# iDProxRev2.net
KiCad netlist of a schematic drawn in Altium Designer
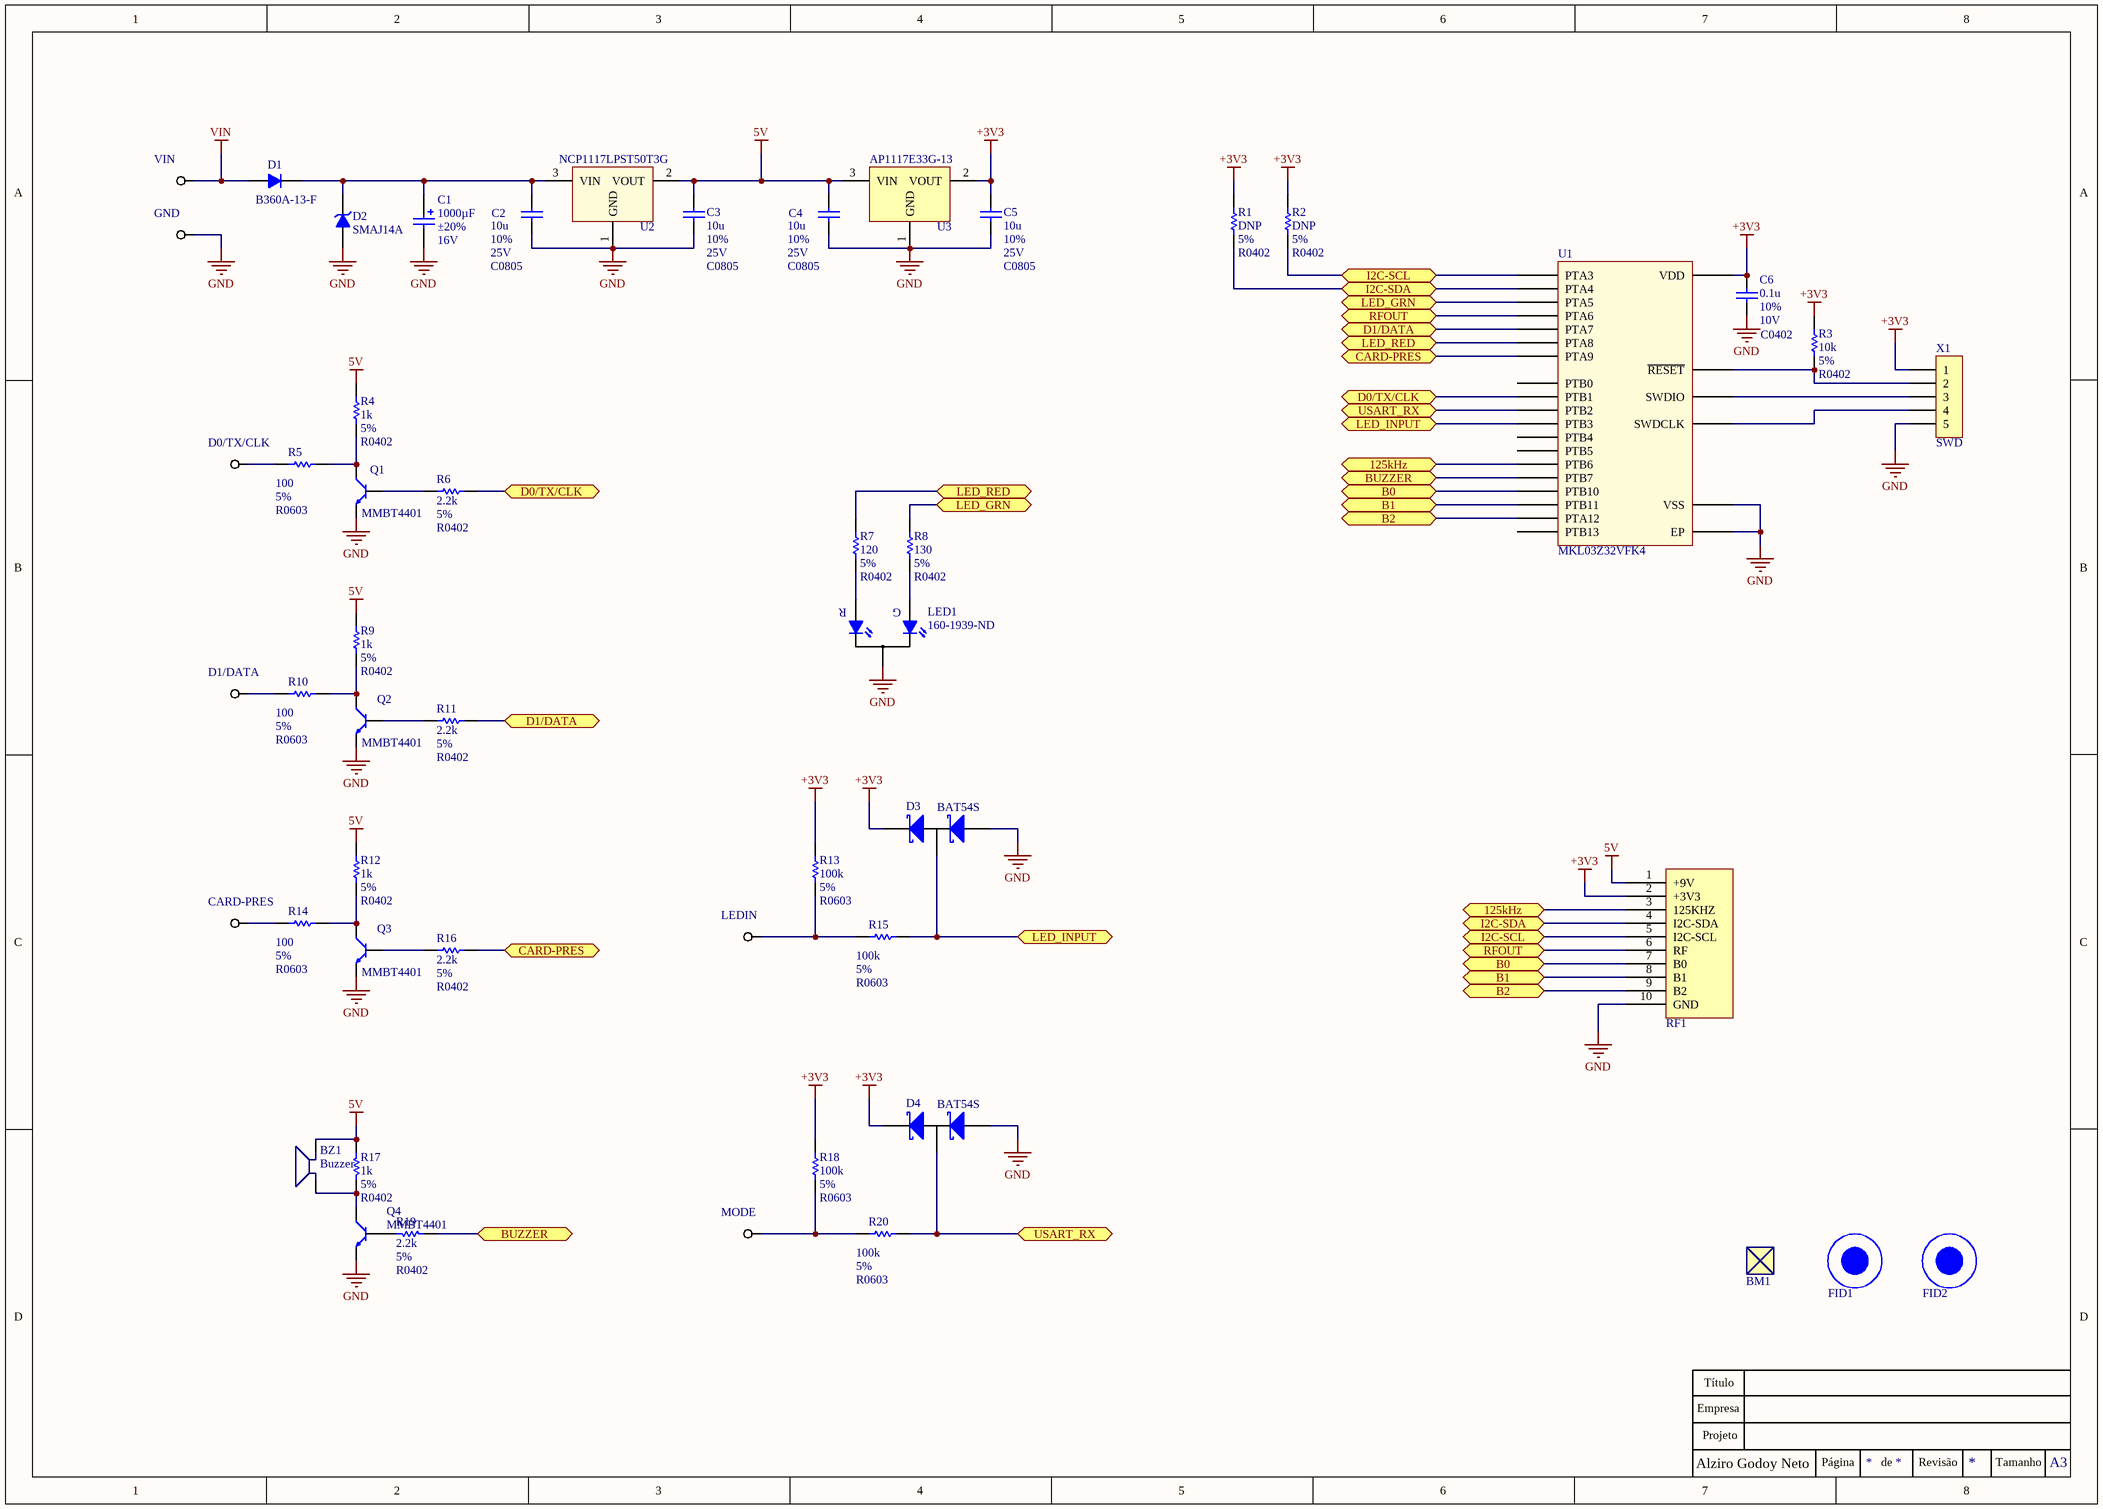
[diagram p0: iDProxRev2.SchDoc]

(export (version "E")
  (design (tool "Eeschema 10.0.6"))
  (components
    (comp (ref "BM1")
      (value "BADMARK")
      (footprint "BADMARK")
      (description "Bad Mark Indicator")
      (libsource (lib "CiDLib") (part "BADMARK"))
    )
    (comp (ref "BZ1")
      (value "Buzzer")
      (footprint "Buzzer")
      (description "Standard PTH Buzzer")
      (libsource (lib "CiDLib") (part "Buzzer"))
    )
    (comp (ref "C1")
      (value "ESK108M016AH2AA")
      (footprint "ESK108M016AH2AA")
      (description "CAP ALUM 1000UF 20% 16V RADIAL")
      (fields
        (field (name "MANUFACTURER") "Kemet")
        (field (name "CAPACITANCE") "1000µF")
        (field (name "TOLERANCE") "±20%")
        (field (name "VOLTAGE RATING") "16V")
      )
      (libsource (lib "CiDLib") (part "ESK108M016AH2AA"))
    )
    (comp (ref "C2")
      (value "10u")
      (footprint "C0805")
      (description "Capacitor")
      (fields
        (field (name "TOLERANCE") "10%")
        (field (name "MAX VDC") "25V")
        (field (name "Comment") "Cap0805")
      )
      (libsource (lib "CiDLib") (part "Cap0805"))
    )
    (comp (ref "C3")
      (value "10u")
      (footprint "C0805")
      (description "Capacitor")
      (fields
        (field (name "TOLERANCE") "10%")
        (field (name "MAX VDC") "25V")
        (field (name "Comment") "Cap0805")
      )
      (libsource (lib "CiDLib") (part "Cap0805"))
    )
    (comp (ref "C4")
      (value "10u")
      (footprint "C0805")
      (description "Capacitor")
      (fields
        (field (name "TOLERANCE") "10%")
        (field (name "MAX VDC") "25V")
        (field (name "Comment") "Cap0805")
      )
      (libsource (lib "CiDLib") (part "Cap0805"))
    )
    (comp (ref "C5")
      (value "10u")
      (footprint "C0805")
      (description "Capacitor")
      (fields
        (field (name "TOLERANCE") "10%")
        (field (name "MAX VDC") "25V")
        (field (name "Comment") "Cap0805")
      )
      (libsource (lib "CiDLib") (part "Cap0805"))
    )
    (comp (ref "C6")
      (value "0.1u")
      (footprint "C0402")
      (description "Capacitor")
      (fields
        (field (name "TOLERANCE") "10%")
        (field (name "MAX VDC") "10V")
        (field (name "Comment") "Cap0402")
      )
      (libsource (lib "CiDLib") (part "Cap0402"))
    )
    (comp (ref "CARD-PRES") (value "Hole") (footprint "Hole") (libsource (lib "CiDLib") (part "Hole")))
    (comp (ref "D0/TX/CLK") (value "Hole") (footprint "Hole") (libsource (lib "CiDLib") (part "Hole")))
    (comp (ref "D1")
      (value "B360A-13-F")
      (footprint "SMA")
      (description "B360A Diode")
      (fields (field (name "MANUFACTURER") "Diodes Incorporated"))
      (libsource (lib "CiDLib") (part "B360A"))
    )
    (comp (ref "D1/DATA") (value "Hole") (footprint "Hole") (libsource (lib "CiDLib") (part "Hole")))
    (comp (ref "D2")
      (value "SMAJ14A")
      (footprint "SMA")
      (description "TVS DIODE 14VWM 23.2VC SMA")
      (fields (field (name "MANUFACTURER") "Littelfuse Inc."))
      (libsource (lib "CiDLib") (part "SMAJ14A"))
    )
    (comp (ref "D3")
      (value "BAT54S")
      (footprint "SOT23-3")
      (description "DIODE ARRAY SCHOTTKY 30V SOT23")
      (libsource (lib "CiDLib") (part "BAT54S"))
    )
    (comp (ref "D4")
      (value "BAT54S")
      (footprint "SOT23-3")
      (description "DIODE ARRAY SCHOTTKY 30V SOT23")
      (libsource (lib "CiDLib") (part "BAT54S"))
    )
    (comp (ref "FID1")
      (value "FIDUCIAL")
      (footprint "FIDUCIAL-1.5X3")
      (description "Standard fiducial for Control iD boards")
      (libsource (lib "CiDLib") (part "FIDUCIAL"))
    )
    (comp (ref "FID2")
      (value "FIDUCIAL")
      (footprint "FIDUCIAL-1.5X3")
      (description "Standard fiducial for Control iD boards")
      (libsource (lib "CiDLib") (part "FIDUCIAL"))
    )
    (comp (ref "GND") (value "Hole") (footprint "Hole") (libsource (lib "CiDLib") (part "Hole")))
    (comp (ref "LED1")
      (value "LTL1BEKVJNN")
      (footprint "LTL1BEKVJNN")
      (description "LED GRN/RED DIFF 3MM ROUND T/H")
      (fields
        (field (name "MANUFACTURER") "Lite-On Inc.")
        (field (name "SUPPLIER PART NUMBER 1") "160-1939-ND")
      )
      (libsource (lib "CiDLib") (part "LTL1BEKVJNN"))
    )
    (comp (ref "LEDIN") (value "Hole") (footprint "Hole") (libsource (lib "CiDLib") (part "Hole")))
    (comp (ref "MODE") (value "Hole") (footprint "Hole") (libsource (lib "CiDLib") (part "Hole")))
    (comp (ref "Q1")
      (value "MMBT4401")
      (footprint "SOT23-3")
      (description "TRANS NPN 40V 0.6A SOT-23")
      (fields
        (field (name "MANUFACTURER") "ON Semiconductor")
        (field (name "MANUFACTURER PART NUMBER") "MMBT4401LT3G")
      )
      (libsource (lib "CiDLib") (part "MMBT4401LT3G"))
    )
    (comp (ref "Q2")
      (value "MMBT4401")
      (footprint "SOT23-3")
      (description "TRANS NPN 40V 0.6A SOT-23")
      (fields
        (field (name "MANUFACTURER") "ON Semiconductor")
        (field (name "MANUFACTURER PART NUMBER") "MMBT4401LT3G")
      )
      (libsource (lib "CiDLib") (part "MMBT4401LT3G"))
    )
    (comp (ref "Q3")
      (value "MMBT4401")
      (footprint "SOT23-3")
      (description "TRANS NPN 40V 0.6A SOT-23")
      (fields
        (field (name "MANUFACTURER") "ON Semiconductor")
        (field (name "MANUFACTURER PART NUMBER") "MMBT4401LT3G")
      )
      (libsource (lib "CiDLib") (part "MMBT4401LT3G"))
    )
    (comp (ref "Q4")
      (value "MMBT4401")
      (footprint "SOT23-3")
      (description "TRANS NPN 40V 0.6A SOT-23")
      (fields
        (field (name "MANUFACTURER") "ON Semiconductor")
        (field (name "MANUFACTURER PART NUMBER") "MMBT4401LT3G")
      )
      (libsource (lib "CiDLib") (part "MMBT4401LT3G"))
    )
    (comp (ref "R1")
      (value "DNP")
      (footprint "R0402")
      (description "Resistor")
      (fields (field (name "TOLERANCE") "5%") (field (name "Comment") "Res0402"))
      (libsource (lib "CiDLib") (part "Res0402"))
    )
    (comp (ref "R2")
      (value "DNP")
      (footprint "R0402")
      (description "Resistor")
      (fields (field (name "TOLERANCE") "5%") (field (name "Comment") "Res0402"))
      (libsource (lib "CiDLib") (part "Res0402"))
    )
    (comp (ref "R3")
      (value "10k")
      (footprint "R0402")
      (description "Resistor")
      (fields (field (name "TOLERANCE") "5%") (field (name "Comment") "Res0402"))
      (libsource (lib "CiDLib") (part "Res0402"))
    )
    (comp (ref "R4")
      (value "1k")
      (footprint "R0402")
      (description "Resistor")
      (fields (field (name "TOLERANCE") "5%") (field (name "Comment") "Res0402"))
      (libsource (lib "CiDLib") (part "Res0402"))
    )
    (comp (ref "R5")
      (value "100")
      (footprint "R0603")
      (description "Resistor")
      (fields (field (name "TOLERANCE") "5%") (field (name "Comment") "Res0603"))
      (libsource (lib "CiDLib") (part "Res0603"))
    )
    (comp (ref "R6")
      (value "2.2k")
      (footprint "R0402")
      (description "Resistor")
      (fields (field (name "TOLERANCE") "5%") (field (name "Comment") "Res0402"))
      (libsource (lib "CiDLib") (part "Res0402"))
    )
    (comp (ref "R7")
      (value "120")
      (footprint "R0402")
      (description "Resistor")
      (fields (field (name "TOLERANCE") "5%") (field (name "Comment") "Res0402"))
      (libsource (lib "CiDLib") (part "Res0402"))
    )
    (comp (ref "R8")
      (value "130")
      (footprint "R0402")
      (description "Resistor")
      (fields (field (name "TOLERANCE") "5%") (field (name "Comment") "Res0402"))
      (libsource (lib "CiDLib") (part "Res0402"))
    )
    (comp (ref "R9")
      (value "1k")
      (footprint "R0402")
      (description "Resistor")
      (fields (field (name "TOLERANCE") "5%") (field (name "Comment") "Res0402"))
      (libsource (lib "CiDLib") (part "Res0402"))
    )
    (comp (ref "R10")
      (value "100")
      (footprint "R0603")
      (description "Resistor")
      (fields (field (name "TOLERANCE") "5%") (field (name "Comment") "Res0603"))
      (libsource (lib "CiDLib") (part "Res0603"))
    )
    (comp (ref "R11")
      (value "2.2k")
      (footprint "R0402")
      (description "Resistor")
      (fields (field (name "TOLERANCE") "5%") (field (name "Comment") "Res0402"))
      (libsource (lib "CiDLib") (part "Res0402"))
    )
    (comp (ref "R12")
      (value "1k")
      (footprint "R0402")
      (description "Resistor")
      (fields (field (name "TOLERANCE") "5%") (field (name "Comment") "Res0402"))
      (libsource (lib "CiDLib") (part "Res0402"))
    )
    (comp (ref "R13")
      (value "100k")
      (footprint "R0603")
      (description "Resistor")
      (fields (field (name "TOLERANCE") "5%") (field (name "Comment") "Res0603"))
      (libsource (lib "CiDLib") (part "Res0603"))
    )
    (comp (ref "R14")
      (value "100")
      (footprint "R0603")
      (description "Resistor")
      (fields (field (name "TOLERANCE") "5%") (field (name "Comment") "Res0603"))
      (libsource (lib "CiDLib") (part "Res0603"))
    )
    (comp (ref "R15")
      (value "100k")
      (footprint "R0603")
      (description "Resistor")
      (fields (field (name "TOLERANCE") "5%") (field (name "Comment") "Res0603"))
      (libsource (lib "CiDLib") (part "Res0603"))
    )
    (comp (ref "R16")
      (value "2.2k")
      (footprint "R0402")
      (description "Resistor")
      (fields (field (name "TOLERANCE") "5%") (field (name "Comment") "Res0402"))
      (libsource (lib "CiDLib") (part "Res0402"))
    )
    (comp (ref "R17")
      (value "1k")
      (footprint "R0402")
      (description "Resistor")
      (fields (field (name "TOLERANCE") "5%") (field (name "Comment") "Res0402"))
      (libsource (lib "CiDLib") (part "Res0402"))
    )
    (comp (ref "R18")
      (value "100k")
      (footprint "R0603")
      (description "Resistor")
      (fields (field (name "TOLERANCE") "5%") (field (name "Comment") "Res0603"))
      (libsource (lib "CiDLib") (part "Res0603"))
    )
    (comp (ref "R19")
      (value "2.2k")
      (footprint "R0402")
      (description "Resistor")
      (fields (field (name "TOLERANCE") "5%") (field (name "Comment") "Res0402"))
      (libsource (lib "CiDLib") (part "Res0402"))
    )
    (comp (ref "R20")
      (value "100k")
      (footprint "R0603")
      (description "Resistor")
      (fields (field (name "TOLERANCE") "5%") (field (name "Comment") "Res0603"))
      (libsource (lib "CiDLib") (part "Res0603"))
    )
    (comp (ref "RF1")
      (value "REPASK/REPMIF")
      (footprint "REPASK/REPMIF")
      (description "Control iD RF Module")
      (libsource (lib "CiDLib") (part "REPASK/REPMIF"))
    )
    (comp (ref "U1")
      (value "MKL03Z32VFK4")
      (footprint "QFN24")
      (description "IC MCU 32BIT 32KB FLASH 24QFN")
      (libsource (lib "CiDLib") (part "MKL03Z32VFK4"))
    )
    (comp (ref "U2")
      (value "NCP1117LPST50T3G")
      (footprint "SOT223")
      (description "IC REG LDO 5V 1A SOT223")
      (fields (field (name "MANUFACTURER") "ON Semiconductor"))
      (libsource (lib "CiDLib") (part "NCP1117LPST50T3G"))
    )
    (comp (ref "U3")
      (value "AP1117E33G-13")
      (footprint "SOT223")
      (libsource (lib "CiDLib") (part "AP1117E33G-13"))
    )
    (comp (ref "VIN") (value "Hole") (footprint "Hole") (libsource (lib "CiDLib") (part "Hole")))
    (comp (ref "X1")
      (value "SWD")
      (footprint "1X05")
      (description "Header, 5-Pin, Single row, 0.1\"")
      (libsource (lib "CiDLib") (part "Header 5"))
    )
  )
  (nets
    (net (code "1") (name "+3V3") (class "Default")
      (node (ref "C5") (pin "2") (pinfunction "2_2") (pintype "passive"))
      (node (ref "C6") (pin "2") (pinfunction "2_2") (pintype "passive"))
      (node (ref "D3") (pin "3") (pinfunction "A1_3") (pintype "passive"))
      (node (ref "D4") (pin "3") (pinfunction "A1_3") (pintype "passive"))
      (node (ref "R1") (pin "2") (pinfunction "2_2") (pintype "passive"))
      (node (ref "R13") (pin "2") (pinfunction "2_2") (pintype "passive"))
      (node (ref "R18") (pin "2") (pinfunction "2_2") (pintype "passive"))
      (node (ref "R2") (pin "2") (pinfunction "2_2") (pintype "passive"))
      (node (ref "R3") (pin "2") (pinfunction "2_2") (pintype "passive"))
      (node (ref "RF1") (pin "2") (pinfunction "+3V3_2") (pintype "passive"))
      (node (ref "U1") (pin "3") (pinfunction "VDD_3") (pintype "passive"))
      (node (ref "U3") (pin "2") (pinfunction "VOUT_2") (pintype "power_in"))
      (node (ref "X1") (pin "1") (pinfunction "1_1") (pintype "passive"))
    )
    (net (code "2") (name "/125kHz") (class "Default")
      (node (ref "RF1") (pin "3") (pinfunction "125KHZ_3") (pintype "passive"))
      (node (ref "U1") (pin "1") (pinfunction "PTB6_1") (pintype "passive"))
    )
    (net (code "3") (name "/B0") (class "Default")
      (node (ref "RF1") (pin "7") (pinfunction "B0_7") (pintype "passive"))
      (node (ref "U1") (pin "9") (pinfunction "PTB10_9") (pintype "passive"))
    )
    (net (code "4") (name "/B1") (class "Default")
      (node (ref "RF1") (pin "8") (pinfunction "B1_8") (pintype "passive"))
      (node (ref "U1") (pin "10") (pinfunction "PTB11_10") (pintype "passive"))
    )
    (net (code "5") (name "/B2") (class "Default")
      (node (ref "RF1") (pin "9") (pinfunction "B2_9") (pintype "passive"))
      (node (ref "U1") (pin "20") (pinfunction "PTA12_20") (pintype "passive"))
    )
    (net (code "6") (name "/BUZZER") (class "Default")
      (node (ref "R19") (pin "2") (pinfunction "2_2") (pintype "passive"))
      (node (ref "U1") (pin "2") (pinfunction "PTB7_2") (pintype "passive"))
    )
    (net (code "7") (name "/CARD-PRES") (class "Default")
      (node (ref "R16") (pin "1") (pinfunction "1_1") (pintype "passive"))
      (node (ref "U1") (pin "16") (pinfunction "PTA9_16") (pintype "passive"))
    )
    (net (code "8") (name "/D0{slash}TX{slash}CLK") (class "Default")
      (node (ref "R6") (pin "1") (pinfunction "1_1") (pintype "passive"))
      (node (ref "U1") (pin "13") (pinfunction "PTB1_13") (pintype "passive"))
    )
    (net (code "9") (name "/D1{slash}DATA") (class "Default")
      (node (ref "R11") (pin "1") (pinfunction "1_1") (pintype "passive"))
      (node (ref "U1") (pin "11") (pinfunction "PTA7_11") (pintype "passive"))
    )
    (net (code "10") (name "/I2C-SCL") (class "Default")
      (node (ref "R2") (pin "1") (pinfunction "1_1") (pintype "passive"))
      (node (ref "RF1") (pin "5") (pinfunction "I2C-SCL_5") (pintype "passive"))
      (node (ref "U1") (pin "5") (pinfunction "PTA3_5") (pintype "passive"))
    )
    (net (code "11") (name "/I2C-SDA") (class "Default")
      (node (ref "R1") (pin "1") (pinfunction "1_1") (pintype "passive"))
      (node (ref "RF1") (pin "4") (pinfunction "I2C-SDA_4") (pintype "passive"))
      (node (ref "U1") (pin "6") (pinfunction "PTA4_6") (pintype "passive"))
    )
    (net (code "12") (name "/LED_GRN") (class "Default")
      (node (ref "R8") (pin "2") (pinfunction "2_2") (pintype "passive"))
      (node (ref "U1") (pin "7") (pinfunction "PTA5_7") (pintype "passive"))
    )
    (net (code "13") (name "/LED_INPUT") (class "Default")
      (node (ref "D3") (pin "1") (pinfunction "K_1") (pintype "passive"))
      (node (ref "R15") (pin "2") (pinfunction "2_2") (pintype "passive"))
      (node (ref "U1") (pin "17") (pinfunction "PTB3_17") (pintype "passive"))
    )
    (net (code "14") (name "/LED_RED") (class "Default")
      (node (ref "R7") (pin "2") (pinfunction "2_2") (pintype "passive"))
      (node (ref "U1") (pin "15") (pinfunction "PTA8_15") (pintype "passive"))
    )
    (net (code "15") (name "/RFOUT") (class "Default")
      (node (ref "RF1") (pin "6") (pinfunction "RF_6") (pintype "passive"))
      (node (ref "U1") (pin "8") (pinfunction "PTA6_8") (pintype "passive"))
    )
    (net (code "16") (name "/USART_RX") (class "Default")
      (node (ref "D4") (pin "1") (pinfunction "K_1") (pintype "passive"))
      (node (ref "R20") (pin "2") (pinfunction "2_2") (pintype "passive"))
      (node (ref "U1") (pin "14") (pinfunction "PTB2_14") (pintype "passive"))
    )
    (net (code "17") (name "5V") (class "Default")
      (node (ref "BZ1") (pin "1") (pinfunction "1_1") (pintype "passive"))
      (node (ref "C3") (pin "2") (pinfunction "2_2") (pintype "passive"))
      (node (ref "C4") (pin "1") (pinfunction "1_1") (pintype "passive"))
      (node (ref "R12") (pin "2") (pinfunction "2_2") (pintype "passive"))
      (node (ref "R17") (pin "2") (pinfunction "2_2") (pintype "passive"))
      (node (ref "R4") (pin "2") (pinfunction "2_2") (pintype "passive"))
      (node (ref "R9") (pin "2") (pinfunction "2_2") (pintype "passive"))
      (node (ref "RF1") (pin "1") (pinfunction "+9V_1") (pintype "passive"))
      (node (ref "U2") (pin "2") (pinfunction "VOUT_2") (pintype "power_in"))
      (node (ref "U3") (pin "3") (pinfunction "VIN_3") (pintype "power_in"))
    )
    (net (code "18") (name "GND") (class "Default")
      (node (ref "C1") (pin "2") (pinfunction "2_2") (pintype "passive"))
      (node (ref "C2") (pin "2") (pinfunction "2_2") (pintype "passive"))
      (node (ref "C3") (pin "1") (pinfunction "1_1") (pintype "passive"))
      (node (ref "C4") (pin "2") (pinfunction "2_2") (pintype "passive"))
      (node (ref "C5") (pin "1") (pinfunction "1_1") (pintype "passive"))
      (node (ref "C6") (pin "1") (pinfunction "1_1") (pintype "passive"))
      (node (ref "D2") (pin "1") (pinfunction "A_1") (pintype "passive"))
      (node (ref "D3") (pin "2") (pinfunction "A2_2") (pintype "passive"))
      (node (ref "D4") (pin "2") (pinfunction "A2_2") (pintype "passive"))
      (node (ref "GND") (pin "1") (pinfunction "1_1") (pintype "passive"))
      (node (ref "LED1") (pin "2") (pinfunction "K_2") (pintype "passive"))
      (node (ref "Q1") (pin "3") (pinfunction "3_3") (pintype "passive"))
      (node (ref "Q2") (pin "3") (pinfunction "3_3") (pintype "passive"))
      (node (ref "Q3") (pin "3") (pinfunction "3_3") (pintype "passive"))
      (node (ref "Q4") (pin "3") (pinfunction "3_3") (pintype "passive"))
      (node (ref "RF1") (pin "10") (pinfunction "GND_10") (pintype "passive"))
      (node (ref "U1") (pin "25") (pinfunction "EP_25") (pintype "passive"))
      (node (ref "U1") (pin "4") (pinfunction "VSS_4") (pintype "passive"))
      (node (ref "U2") (pin "1") (pinfunction "GND_1") (pintype "power_in"))
      (node (ref "U3") (pin "1") (pinfunction "GND_1") (pintype "power_in"))
      (node (ref "X1") (pin "5") (pinfunction "5_5") (pintype "passive"))
    )
    (net (code "19") (name "Net-(BZ1-Pad2)") (class "Default")
      (node (ref "BZ1") (pin "2") (pinfunction "2_2") (pintype "passive"))
      (node (ref "Q4") (pin "1") (pinfunction "1_1") (pintype "passive"))
      (node (ref "R17") (pin "1") (pinfunction "1_1") (pintype "passive"))
    )
    (net (code "20") (name "Net-(CARD-PRES-Pad1)") (class "Default")
      (node (ref "CARD-PRES") (pin "1") (pinfunction "1_1") (pintype "passive"))
      (node (ref "R14") (pin "1") (pinfunction "1_1") (pintype "passive"))
    )
    (net (code "21") (name "Net-(D0/TX/CLK-Pad1)") (class "Default")
      (node (ref "D0/TX/CLK") (pin "1") (pinfunction "1_1") (pintype "passive"))
      (node (ref "R5") (pin "1") (pinfunction "1_1") (pintype "passive"))
    )
    (net (code "22") (name "Net-(D1-K)") (class "Default")
      (node (ref "C1") (pin "1") (pinfunction "1_1") (pintype "passive"))
      (node (ref "C2") (pin "1") (pinfunction "1_1") (pintype "passive"))
      (node (ref "D1") (pin "2") (pinfunction "K_2") (pintype "passive"))
      (node (ref "D2") (pin "2") (pinfunction "K_2") (pintype "passive"))
      (node (ref "U2") (pin "3") (pinfunction "VIN_3") (pintype "power_in"))
    )
    (net (code "23") (name "Net-(D1/DATA-Pad1)") (class "Default")
      (node (ref "D1/DATA") (pin "1") (pinfunction "1_1") (pintype "passive"))
      (node (ref "R10") (pin "1") (pinfunction "1_1") (pintype "passive"))
    )
    (net (code "24") (name "Net-(LED1-AG)") (class "Default")
      (node (ref "LED1") (pin "3") (pinfunction "AG_3") (pintype "passive"))
      (node (ref "R8") (pin "1") (pinfunction "1_1") (pintype "passive"))
    )
    (net (code "25") (name "Net-(LED1-AR)") (class "Default")
      (node (ref "LED1") (pin "1") (pinfunction "AR_1") (pintype "passive"))
      (node (ref "R7") (pin "1") (pinfunction "1_1") (pintype "passive"))
    )
    (net (code "26") (name "Net-(LEDIN-Pad1)") (class "Default")
      (node (ref "LEDIN") (pin "1") (pinfunction "1_1") (pintype "passive"))
      (node (ref "R13") (pin "1") (pinfunction "1_1") (pintype "passive"))
      (node (ref "R15") (pin "1") (pinfunction "1_1") (pintype "passive"))
    )
    (net (code "27") (name "Net-(MODE-Pad1)") (class "Default")
      (node (ref "MODE") (pin "1") (pinfunction "1_1") (pintype "passive"))
      (node (ref "R18") (pin "1") (pinfunction "1_1") (pintype "passive"))
      (node (ref "R20") (pin "1") (pinfunction "1_1") (pintype "passive"))
    )
    (net (code "28") (name "Net-(Q1-Pad1)") (class "Default")
      (node (ref "Q1") (pin "1") (pinfunction "1_1") (pintype "passive"))
      (node (ref "R4") (pin "1") (pinfunction "1_1") (pintype "passive"))
      (node (ref "R5") (pin "2") (pinfunction "2_2") (pintype "passive"))
    )
    (net (code "29") (name "Net-(Q1-Pad2)") (class "Default")
      (node (ref "Q1") (pin "2") (pinfunction "2_2") (pintype "passive"))
      (node (ref "R6") (pin "2") (pinfunction "2_2") (pintype "passive"))
    )
    (net (code "30") (name "Net-(Q2-Pad1)") (class "Default")
      (node (ref "Q2") (pin "1") (pinfunction "1_1") (pintype "passive"))
      (node (ref "R10") (pin "2") (pinfunction "2_2") (pintype "passive"))
      (node (ref "R9") (pin "1") (pinfunction "1_1") (pintype "passive"))
    )
    (net (code "31") (name "Net-(Q2-Pad2)") (class "Default")
      (node (ref "Q2") (pin "2") (pinfunction "2_2") (pintype "passive"))
      (node (ref "R11") (pin "2") (pinfunction "2_2") (pintype "passive"))
    )
    (net (code "32") (name "Net-(Q3-Pad1)") (class "Default")
      (node (ref "Q3") (pin "1") (pinfunction "1_1") (pintype "passive"))
      (node (ref "R12") (pin "1") (pinfunction "1_1") (pintype "passive"))
      (node (ref "R14") (pin "2") (pinfunction "2_2") (pintype "passive"))
    )
    (net (code "33") (name "Net-(Q3-Pad2)") (class "Default")
      (node (ref "Q3") (pin "2") (pinfunction "2_2") (pintype "passive"))
      (node (ref "R16") (pin "2") (pinfunction "2_2") (pintype "passive"))
    )
    (net (code "34") (name "Net-(Q4-Pad2)") (class "Default")
      (node (ref "Q4") (pin "2") (pinfunction "2_2") (pintype "passive"))
      (node (ref "R19") (pin "1") (pinfunction "1_1") (pintype "passive"))
    )
    (net (code "35") (name "Net-(U1-SWDCLK)") (class "Default")
      (node (ref "U1") (pin "22") (pinfunction "SWDCLK_22") (pintype "passive"))
      (node (ref "X1") (pin "4") (pinfunction "4_4") (pintype "passive"))
    )
    (net (code "36") (name "Net-(U1-SWDIO)") (class "Default")
      (node (ref "U1") (pin "24") (pinfunction "SWDIO_24") (pintype "passive"))
      (node (ref "X1") (pin "3") (pinfunction "3_3") (pintype "passive"))
    )
    (net (code "37") (name "Net-(U1-~{RESET})") (class "Default")
      (node (ref "R3") (pin "1") (pinfunction "1_1") (pintype "passive"))
      (node (ref "U1") (pin "23") (pinfunction "~{RESET}_23") (pintype "passive"))
      (node (ref "X1") (pin "2") (pinfunction "2_2") (pintype "passive"))
    )
    (net (code "38") (name "VIN") (class "Default")
      (node (ref "D1") (pin "1") (pinfunction "A_1") (pintype "passive"))
      (node (ref "VIN") (pin "1") (pinfunction "1_1") (pintype "passive"))
    )
    (net (code "39") (name "unconnected-(U1-PTB0-Pad12)") (class "Default")
      (node (ref "U1") (pin "12") (pinfunction "PTB0_12") (pintype "passive"))
    )
    (net (code "40") (name "unconnected-(U1-PTB4-Pad18)") (class "Default")
      (node (ref "U1") (pin "18") (pinfunction "PTB4_18") (pintype "passive"))
    )
    (net (code "41") (name "unconnected-(U1-PTB5-Pad19)") (class "Default")
      (node (ref "U1") (pin "19") (pinfunction "PTB5_19") (pintype "passive"))
    )
    (net (code "42") (name "unconnected-(U1-PTB13-Pad21)") (class "Default")
      (node (ref "U1") (pin "21") (pinfunction "PTB13_21") (pintype "passive"))
    )
  )
)
